# RF_I2C_EEPROM.net
KiCad netlist of a schematic drawn in Altium Designer
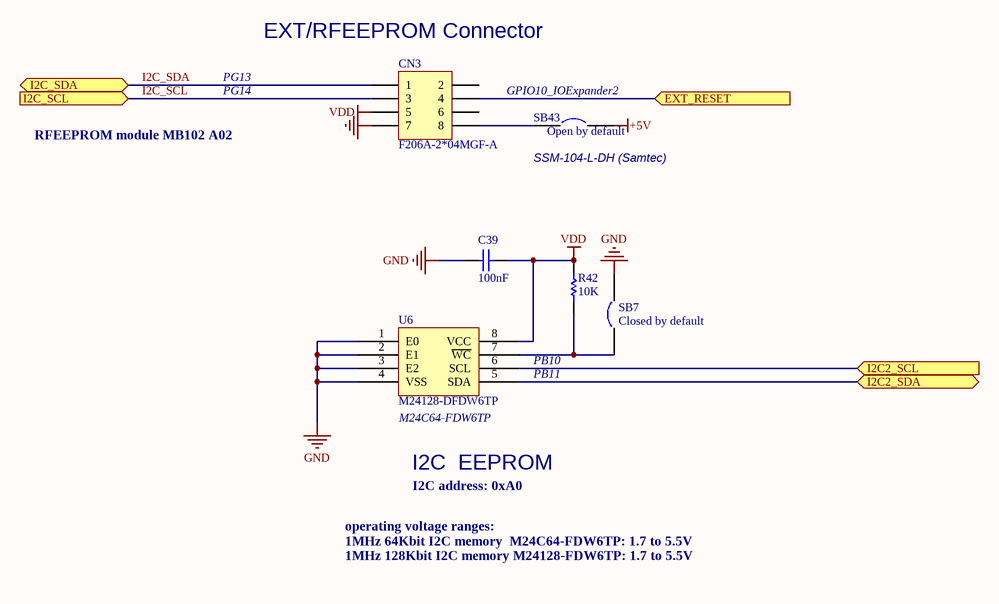
[diagram p0: RF_I2C_EEPROM.SchDoc]

(export (version "E")
  (design (tool "Eeschema 10.0.6"))
  (components
    (comp (ref "C39")
      (value "100nF")
      (footprint "0402C")
      (description "Capacitor")
      (fields (field (name "PUBLISHER") "Altium Limited"))
      (libsource (lib "orcaeval_2") (part "CAP"))
    )
    (comp (ref "CN3")
      (value "F206A-2*04MGF-A")
      (footprint "SSM-104-L-DH")
      (description "Header, 5-Pin, Dual row")
      (fields (field (name "PUBLISHER") "Altium Limited"))
      (libsource (lib "mb1045") (part "SSM-104-L-DH"))
    )
    (comp (ref "R42")
      (value "10K")
      (footprint "0402R")
      (description "Resistor")
      (fields (field (name "PUBLISHER") "Altium Limited"))
      (libsource (lib "Miscellaneous Devices") (part "Res1"))
    )
    (comp (ref "SB7")
      (value "Closed by default")
      (footprint "SB_0603")
      (description "Circuit Breaker")
      (fields (field (name "PUBLISHER") "Altium Limited"))
      (libsource (lib "Miscellaneous Devices") (part "Circuit Breaker"))
    )
    (comp (ref "SB43")
      (value "Open by default")
      (footprint "SB_0603")
      (description "Circuit Breaker")
      (fields (field (name "PUBLISHER") "Altium Limited"))
      (libsource (lib "Miscellaneous Devices") (part "Circuit Breaker"))
    )
    (comp (ref "U6")
      (value "M24128-DFDW6TP")
      (footprint "TSSOP8_0R65_3X6R4")
      (libsource (lib "ST79F5xx-EVAL") (part "M24C64-WMN6"))
    )
  )
  (nets
    (net (code "1") (name "+5V") (class "Default")
      (node (ref "SB43") (pin "2") (pinfunction "2_2") (pintype "passive"))
    )
    (net (code "2") (name "/EXT_RESET") (class "Default")
      (node (ref "CN3") (pin "4") (pinfunction "4_4") (pintype "passive"))
    )
    (net (code "3") (name "/I2C2_SCL") (class "Default")
      (node (ref "U6") (pin "6") (pinfunction "SCL_6") (pintype "passive"))
    )
    (net (code "4") (name "/I2C2_SDA") (class "Default")
      (node (ref "U6") (pin "5") (pinfunction "SDA_5") (pintype "passive"))
    )
    (net (code "5") (name "/I2C_SCL") (class "Default")
      (node (ref "CN3") (pin "3") (pinfunction "3_3") (pintype "passive"))
    )
    (net (code "6") (name "/I2C_SDA") (class "Default")
      (node (ref "CN3") (pin "1") (pinfunction "1_1") (pintype "passive"))
    )
    (net (code "7") (name "GND") (class "Default")
      (node (ref "C39") (pin "1") (pinfunction "1_1") (pintype "passive"))
      (node (ref "CN3") (pin "7") (pinfunction "7_7") (pintype "passive"))
      (node (ref "SB7") (pin "2") (pinfunction "2_2") (pintype "passive"))
      (node (ref "U6") (pin "1") (pinfunction "E0_1") (pintype "passive"))
      (node (ref "U6") (pin "2") (pinfunction "E1_2") (pintype "passive"))
      (node (ref "U6") (pin "3") (pinfunction "E2_3") (pintype "passive"))
      (node (ref "U6") (pin "4") (pinfunction "VSS_4") (pintype "passive"))
    )
    (net (code "8") (name "Net-(CN3-Pad8)") (class "Default")
      (node (ref "CN3") (pin "8") (pinfunction "8_8") (pintype "passive"))
      (node (ref "SB43") (pin "1") (pinfunction "1_1") (pintype "passive"))
    )
    (net (code "9") (name "Net-(U6-~{WC})") (class "Default")
      (node (ref "R42") (pin "2") (pinfunction "2_2") (pintype "passive"))
      (node (ref "SB7") (pin "1") (pinfunction "1_1") (pintype "passive"))
      (node (ref "U6") (pin "7") (pinfunction "~{WC}_7") (pintype "passive"))
    )
    (net (code "10") (name "VDD") (class "Default")
      (node (ref "C39") (pin "2") (pinfunction "2_2") (pintype "passive"))
      (node (ref "CN3") (pin "5") (pinfunction "5_5") (pintype "passive"))
      (node (ref "R42") (pin "1") (pinfunction "1_1") (pintype "passive"))
      (node (ref "U6") (pin "8") (pinfunction "VCC_8") (pintype "passive"))
    )
    (net (code "11") (name "unconnected-(CN3-Pad2)") (class "Default")
      (node (ref "CN3") (pin "2") (pinfunction "2_2") (pintype "passive"))
    )
    (net (code "12") (name "unconnected-(CN3-Pad6)") (class "Default")
      (node (ref "CN3") (pin "6") (pinfunction "6_6") (pintype "passive"))
    )
  )
)
